# main.net
KiCad netlist of a schematic drawn in Altium Designer
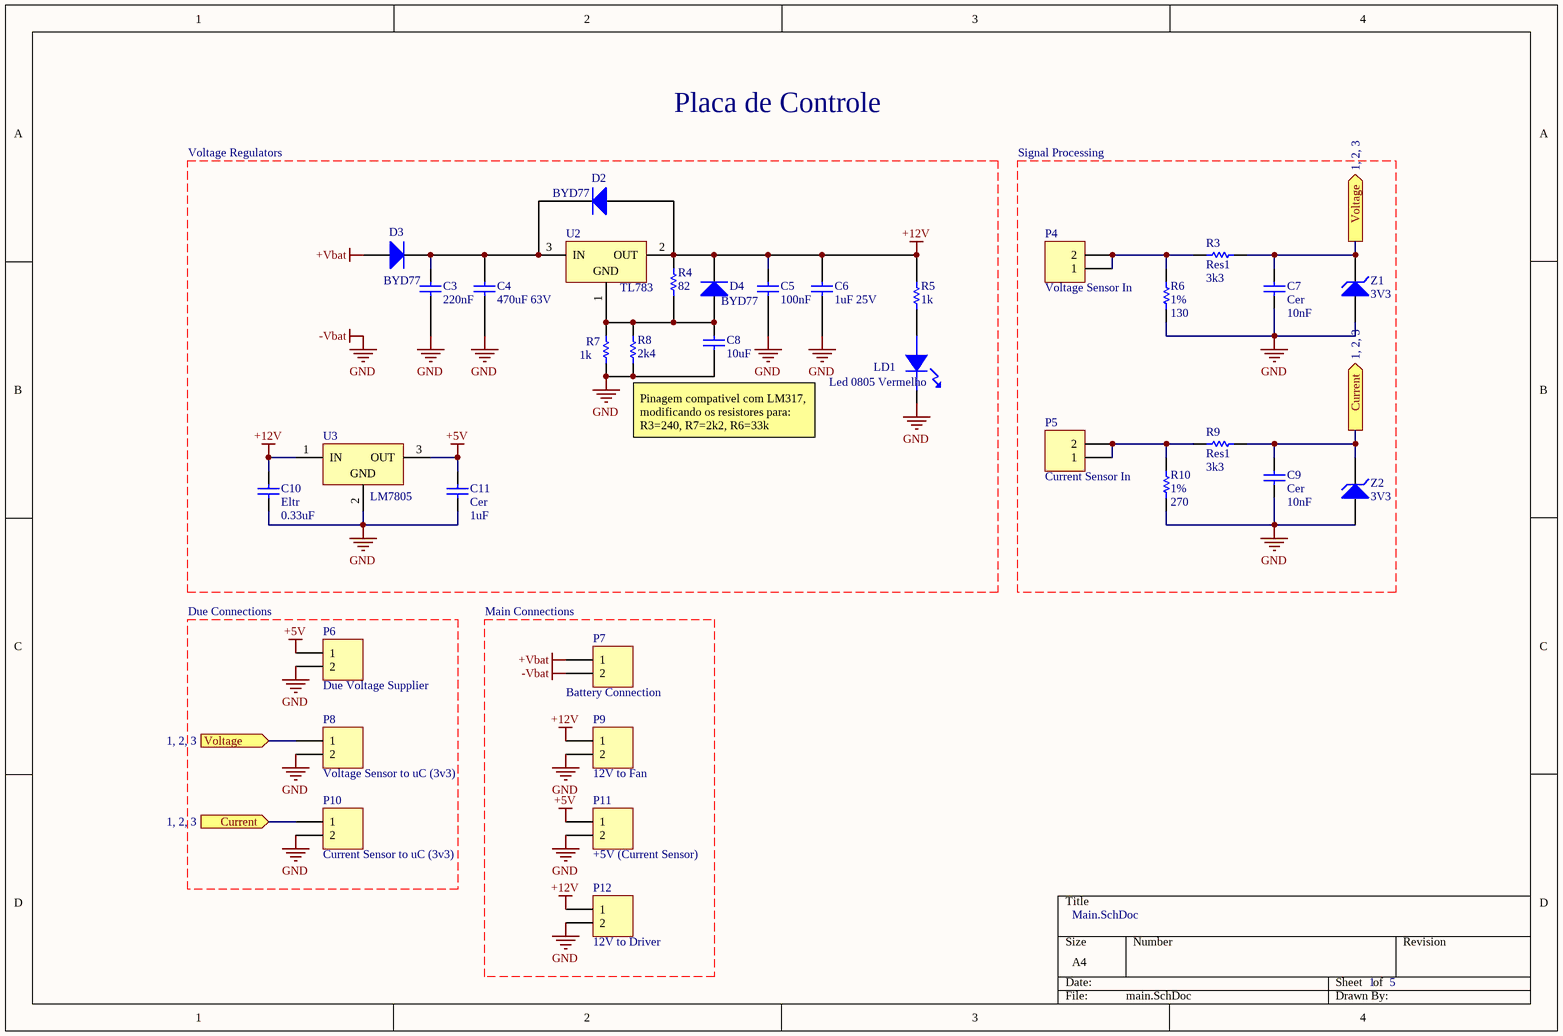
[diagram p0: main.SchDoc]

(export (version "E")
  (design (tool "Eeschema 10.0.6"))
  (components
    (comp (ref "C3")
      (value "220nF")
      (footprint "RESC2012M")
      (description "Capacitor")
      (fields (field (name "Comment") "Cap") (field (name "PUBLISHER") "Altium Limited"))
      (libsource (lib "Miscellaneous Devices") (part "Cap"))
    )
    (comp (ref "C4")
      (value "470uF 63V")
      (footprint "CapEltr-Rad6.6-Dpp4.5")
      (description "Capacitor")
      (fields (field (name "Comment") "Cap") (field (name "PUBLISHER") "Altium Limited"))
      (libsource (lib "Miscellaneous Devices") (part "Cap"))
    )
    (comp (ref "C5")
      (value "100nF")
      (footprint "CAPC2012L")
      (description "Capacitor")
      (fields (field (name "Comment") "Cap") (field (name "PUBLISHER") "Altium Limited"))
      (libsource (lib "Miscellaneous Devices") (part "Cap"))
    )
    (comp (ref "C6")
      (value "1uF 25V")
      (footprint "CapEltr-Rad4.1-Dpp3.0")
      (description "Capacitor")
      (fields (field (name "Comment") "Cap") (field (name "PUBLISHER") "Altium Limited"))
      (libsource (lib "Miscellaneous Devices") (part "Cap"))
    )
    (comp (ref "C7")
      (value "Cer")
      (footprint "CAPC2012L")
      (description "Capacitor")
      (fields (field (name "ALTIUM_VALUE") "10nF") (field (name "PUBLISHER") "Altium Limited"))
      (libsource (lib "Miscellaneous Devices") (part "Cap"))
    )
    (comp (ref "C8")
      (value "10uF")
      (footprint "CAPC2012L")
      (description "Capacitor")
      (fields (field (name "Comment") "Cap") (field (name "PUBLISHER") "Altium Limited"))
      (libsource (lib "Miscellaneous Devices") (part "Cap"))
    )
    (comp (ref "C9")
      (value "Cer")
      (footprint "CAPC2012L")
      (description "Capacitor")
      (fields (field (name "ALTIUM_VALUE") "10nF") (field (name "PUBLISHER") "Altium Limited"))
      (libsource (lib "Miscellaneous Devices") (part "Cap"))
    )
    (comp (ref "C10")
      (value "Eltr")
      (footprint "cap33n63v")
      (description "Capacitor")
      (fields (field (name "ALTIUM_VALUE") "0.33uF") (field (name "PUBLISHER") "Altium Limited"))
      (libsource (lib "Miscellaneous Devices") (part "Cap"))
    )
    (comp (ref "C11")
      (value "Cer")
      (footprint "1u25v")
      (description "Capacitor")
      (fields (field (name "ALTIUM_VALUE") "1uF") (field (name "PUBLISHER") "Altium Limited"))
      (libsource (lib "Miscellaneous Devices") (part "Cap"))
    )
    (comp (ref "D2")
      (value "BYD77")
      (footprint "SOD87")
      (description "1 Amp General Purpose Rectifier")
      (fields (field (name "PUBLISHER") "Altium Limited"))
      (libsource (lib "Miscellaneous Devices") (part "Diode 1N4002"))
    )
    (comp (ref "D3")
      (value "BYD77")
      (footprint "SOD87")
      (description "1 Amp General Purpose Rectifier")
      (fields (field (name "Comment") "Diode 1N4002") (field (name "PUBLISHER") "Altium Limited"))
      (libsource (lib "Miscellaneous Devices") (part "Diode 1N4002"))
    )
    (comp (ref "D4")
      (value "BYD77")
      (footprint "SOD87")
      (description "1 Amp General Purpose Rectifier")
      (fields (field (name "Comment") "1N4002") (field (name "PUBLISHER") "Altium Limited"))
      (libsource (lib "Miscellaneous Devices") (part "Diode 1N4002"))
    )
    (comp (ref "LD1")
      (value "Led 0805 Vermelho")
      (footprint "RESC2012M")
      (description "Diodo Emissor de Luz")
      (fields (field (name "Comment") "RED"))
      (libsource (lib "Biblioteca_Guilherme") (part "LED"))
    )
    (comp (ref "P4")
      (value "Voltage Sensor In")
      (footprint "HDR1X2")
      (description "Header, 2-Pin")
      (fields (field (name "PUBLISHER") "Altium Limited"))
      (libsource (lib "") (part "Header 2_1"))
    )
    (comp (ref "P5")
      (value "Current Sensor In")
      (footprint "HDR1X2")
      (description "Header, 2-Pin")
      (fields (field (name "PUBLISHER") "Altium Limited"))
      (libsource (lib "") (part "Header 2_1"))
    )
    (comp (ref "P6")
      (value "Due Voltage Supplier")
      (footprint "HDR1X2")
      (description "Header, 2-Pin")
      (fields (field (name "PUBLISHER") "Altium Limited"))
      (libsource (lib "Miscellaneous Connectors") (part "Header 2"))
    )
    (comp (ref "P7")
      (value "Battery Connection")
      (footprint "HDR1X2")
      (description "Header, 2-Pin")
      (fields (field (name "PUBLISHER") "Altium Limited"))
      (libsource (lib "Miscellaneous Connectors") (part "Header 2"))
    )
    (comp (ref "P8")
      (value "Voltage Sensor to uC (3v3)")
      (footprint "HDR1X2")
      (description "Header, 2-Pin")
      (fields (field (name "PUBLISHER") "Altium Limited"))
      (libsource (lib "Miscellaneous Connectors") (part "Header 2"))
    )
    (comp (ref "P9")
      (value "12V to Fan")
      (footprint "HDR1X2")
      (description "Header, 2-Pin")
      (fields (field (name "PUBLISHER") "Altium Limited"))
      (libsource (lib "Miscellaneous Connectors") (part "Header 2"))
    )
    (comp (ref "P10")
      (value "Current Sensor to uC (3v3)")
      (footprint "HDR1X2")
      (description "Header, 2-Pin")
      (fields (field (name "PUBLISHER") "Altium Limited"))
      (libsource (lib "Miscellaneous Connectors") (part "Header 2"))
    )
    (comp (ref "P11")
      (value "+5V (Current Sensor)")
      (footprint "HDR1X2")
      (description "Header, 2-Pin")
      (fields (field (name "PUBLISHER") "Altium Limited"))
      (libsource (lib "Miscellaneous Connectors") (part "Header 2"))
    )
    (comp (ref "P12")
      (value "12V to Driver")
      (footprint "HDR1X2")
      (description "Header, 2-Pin")
      (fields (field (name "PUBLISHER") "Altium Limited"))
      (libsource (lib "Miscellaneous Connectors") (part "Header 2"))
    )
    (comp (ref "R3")
      (value "Res1")
      (footprint "RESC2012M")
      (description "Resistor")
      (fields (field (name "ALTIUM_VALUE") "3k3") (field (name "PUBLISHER") "Altium Limited"))
      (libsource (lib "Miscellaneous Devices") (part "Res1"))
    )
    (comp (ref "R4")
      (value "82")
      (footprint "RESC2012M")
      (description "Resistor")
      (fields (field (name "Comment") "Res1") (field (name "PUBLISHER") "Altium Limited"))
      (libsource (lib "Miscellaneous Devices") (part "Res1"))
    )
    (comp (ref "R5")
      (value "1k")
      (footprint "RESC2012M")
      (description "Resistor")
      (fields (field (name "Comment") "Res1") (field (name "PUBLISHER") "Altium Limited"))
      (libsource (lib "Miscellaneous Devices") (part "Res1"))
    )
    (comp (ref "R6")
      (value "1%")
      (footprint "RESC2012M")
      (description "Resistor")
      (fields (field (name "ALTIUM_VALUE") "130") (field (name "PUBLISHER") "Altium Limited"))
      (libsource (lib "Miscellaneous Devices") (part "Res1"))
    )
    (comp (ref "R7")
      (value "1k")
      (footprint "RESC2012M")
      (description "Resistor")
      (fields (field (name "Comment") "Res1") (field (name "PUBLISHER") "Altium Limited"))
      (libsource (lib "Miscellaneous Devices") (part "Res1"))
    )
    (comp (ref "R8")
      (value "2k4")
      (footprint "RESC2012M")
      (description "Resistor")
      (fields (field (name "Comment") "Res1") (field (name "PUBLISHER") "Altium Limited"))
      (libsource (lib "Miscellaneous Devices") (part "Res1"))
    )
    (comp (ref "R9")
      (value "Res1")
      (footprint "RESC2012M")
      (description "Resistor")
      (fields (field (name "ALTIUM_VALUE") "3k3") (field (name "PUBLISHER") "Altium Limited"))
      (libsource (lib "Miscellaneous Devices") (part "Res1"))
    )
    (comp (ref "R10")
      (value "1%")
      (footprint "RESC2012M")
      (description "Resistor")
      (fields (field (name "ALTIUM_VALUE") "270") (field (name "PUBLISHER") "Altium Limited"))
      (libsource (lib "Miscellaneous Devices") (part "Res1"))
    )
    (comp (ref "U2")
      (value "TL783")
      (footprint "TO-220AB")
      (description "Precision 1A Regulator")
      (fields (field (name "PUBLISHER") "Altium Limited"))
      (libsource (lib "ST Power Mgt Voltage Regulator") (part "L7805ACV"))
    )
    (comp (ref "U3")
      (value "LM7805")
      (footprint "TO-220AB")
      (description "Positive-Voltage Regulator")
      (fields (field (name "PUBLISHER") "Altium Limited"))
      (libsource (lib "TI Power Mgt Voltage Regulator") (part "µA7805CKC"))
    )
    (comp (ref "Z1")
      (value "3V3")
      (footprint "DO-41")
      (description "Zener Diode")
      (fields (field (name "PUBLISHER") "Altium Limited"))
      (libsource (lib "Miscellaneous Devices") (part "D Zener"))
    )
    (comp (ref "Z2")
      (value "3V3")
      (footprint "DO-41")
      (description "Zener Diode")
      (fields (field (name "PUBLISHER") "Altium Limited"))
      (libsource (lib "Miscellaneous Devices") (part "D Zener"))
    )
  )
  (nets
    (net (code "1") (name "+5V") (class "Default")
      (node (ref "C11") (pin "2") (pinfunction "2_2") (pintype "passive"))
      (node (ref "P11") (pin "1") (pinfunction "1_1") (pintype "passive"))
      (node (ref "P6") (pin "1") (pinfunction "1_1") (pintype "passive"))
      (node (ref "U3") (pin "3") (pinfunction "OUT_3") (pintype "power_in"))
    )
    (net (code "2") (name "+12V") (class "Default")
      (node (ref "C10") (pin "2") (pinfunction "2_2") (pintype "passive"))
      (node (ref "C5") (pin "2") (pinfunction "2_2") (pintype "passive"))
      (node (ref "C6") (pin "2") (pinfunction "2_2") (pintype "passive"))
      (node (ref "D2") (pin "1") (pinfunction "A_1") (pintype "passive"))
      (node (ref "D4") (pin "2") (pinfunction "K_2") (pintype "passive"))
      (node (ref "P12") (pin "1") (pinfunction "1_1") (pintype "passive"))
      (node (ref "P9") (pin "1") (pinfunction "1_1") (pintype "passive"))
      (node (ref "R4") (pin "1") (pinfunction "1_1") (pintype "passive"))
      (node (ref "R5") (pin "2") (pinfunction "2_2") (pintype "passive"))
      (node (ref "U2") (pin "2") (pinfunction "OUT_2") (pintype "power_in"))
      (node (ref "U3") (pin "1") (pinfunction "IN_1") (pintype "power_in"))
    )
    (net (code "3") (name "+Vbat") (class "Default")
      (node (ref "D3") (pin "1") (pinfunction "A_1") (pintype "passive"))
      (node (ref "P7") (pin "1") (pinfunction "1_1") (pintype "passive"))
    )
    (net (code "4") (name "-Vbat") (class "Default")
      (node (ref "C10") (pin "1") (pinfunction "1_1") (pintype "passive"))
      (node (ref "C11") (pin "1") (pinfunction "1_1") (pintype "passive"))
      (node (ref "C3") (pin "1") (pinfunction "1_1") (pintype "passive"))
      (node (ref "C4") (pin "1") (pinfunction "1_1") (pintype "passive"))
      (node (ref "C5") (pin "1") (pinfunction "1_1") (pintype "passive"))
      (node (ref "C6") (pin "1") (pinfunction "1_1") (pintype "passive"))
      (node (ref "C7") (pin "1") (pinfunction "1_1") (pintype "passive"))
      (node (ref "C8") (pin "1") (pinfunction "1_1") (pintype "passive"))
      (node (ref "C9") (pin "1") (pinfunction "1_1") (pintype "passive"))
      (node (ref "LD1") (pin "2") (pinfunction "2_2") (pintype "passive"))
      (node (ref "P10") (pin "2") (pinfunction "2_2") (pintype "passive"))
      (node (ref "P11") (pin "2") (pinfunction "2_2") (pintype "passive"))
      (node (ref "P12") (pin "2") (pinfunction "2_2") (pintype "passive"))
      (node (ref "P6") (pin "2") (pinfunction "2_2") (pintype "passive"))
      (node (ref "P7") (pin "2") (pinfunction "2_2") (pintype "passive"))
      (node (ref "P8") (pin "2") (pinfunction "2_2") (pintype "passive"))
      (node (ref "P9") (pin "2") (pinfunction "2_2") (pintype "passive"))
      (node (ref "R10") (pin "1") (pinfunction "1_1") (pintype "passive"))
      (node (ref "R6") (pin "1") (pinfunction "1_1") (pintype "passive"))
      (node (ref "R7") (pin "1") (pinfunction "1_1") (pintype "passive"))
      (node (ref "R8") (pin "1") (pinfunction "1_1") (pintype "passive"))
      (node (ref "U3") (pin "2") (pinfunction "GND_2") (pintype "power_in"))
      (node (ref "Z1") (pin "1") (pinfunction "A_1") (pintype "passive"))
      (node (ref "Z2") (pin "1") (pinfunction "A_1") (pintype "passive"))
    )
    (net (code "5") (name "/Current") (class "Default")
      (node (ref "C9") (pin "2") (pinfunction "2_2") (pintype "passive"))
      (node (ref "P10") (pin "1") (pinfunction "1_1") (pintype "passive"))
      (node (ref "R9") (pin "2") (pinfunction "2_2") (pintype "passive"))
      (node (ref "Z2") (pin "2") (pinfunction "K_2") (pintype "passive"))
    )
    (net (code "6") (name "/Voltage") (class "Default")
      (node (ref "C7") (pin "2") (pinfunction "2_2") (pintype "passive"))
      (node (ref "P8") (pin "1") (pinfunction "1_1") (pintype "passive"))
      (node (ref "R3") (pin "2") (pinfunction "2_2") (pintype "passive"))
      (node (ref "Z1") (pin "2") (pinfunction "K_2") (pintype "passive"))
    )
    (net (code "7") (name "Net-(D2-K)") (class "Default")
      (node (ref "C3") (pin "2") (pinfunction "2_2") (pintype "passive"))
      (node (ref "C4") (pin "2") (pinfunction "2_2") (pintype "passive"))
      (node (ref "D2") (pin "2") (pinfunction "K_2") (pintype "passive"))
      (node (ref "D3") (pin "2") (pinfunction "K_2") (pintype "passive"))
      (node (ref "U2") (pin "3") (pinfunction "IN_3") (pintype "power_in"))
    )
    (net (code "8") (name "Net-(D4-A)") (class "Default")
      (node (ref "C8") (pin "2") (pinfunction "2_2") (pintype "passive"))
      (node (ref "D4") (pin "1") (pinfunction "A_1") (pintype "passive"))
      (node (ref "R4") (pin "2") (pinfunction "2_2") (pintype "passive"))
      (node (ref "R7") (pin "2") (pinfunction "2_2") (pintype "passive"))
      (node (ref "R8") (pin "2") (pinfunction "2_2") (pintype "passive"))
      (node (ref "U2") (pin "1") (pinfunction "ADJ_1") (pintype "power_in"))
    )
    (net (code "9") (name "Net-(LD1-Pad1)") (class "Default")
      (node (ref "LD1") (pin "1") (pinfunction "1_1") (pintype "passive"))
      (node (ref "R5") (pin "1") (pinfunction "1_1") (pintype "passive"))
    )
    (net (code "10") (name "Net-(P4-Pad1)") (class "Default")
      (node (ref "P4") (pin "1") (pinfunction "1_1") (pintype "passive"))
      (node (ref "P4") (pin "2") (pinfunction "2_2") (pintype "passive"))
      (node (ref "R3") (pin "1") (pinfunction "1_1") (pintype "passive"))
      (node (ref "R6") (pin "2") (pinfunction "2_2") (pintype "passive"))
    )
    (net (code "11") (name "Net-(P5-Pad1)") (class "Default")
      (node (ref "P5") (pin "1") (pinfunction "1_1") (pintype "passive"))
      (node (ref "P5") (pin "2") (pinfunction "2_2") (pintype "passive"))
      (node (ref "R10") (pin "2") (pinfunction "2_2") (pintype "passive"))
      (node (ref "R9") (pin "1") (pinfunction "1_1") (pintype "passive"))
    )
  )
)
